# two_pieceboard_1.net
KiCad netlist of a schematic drawn in EAGLE
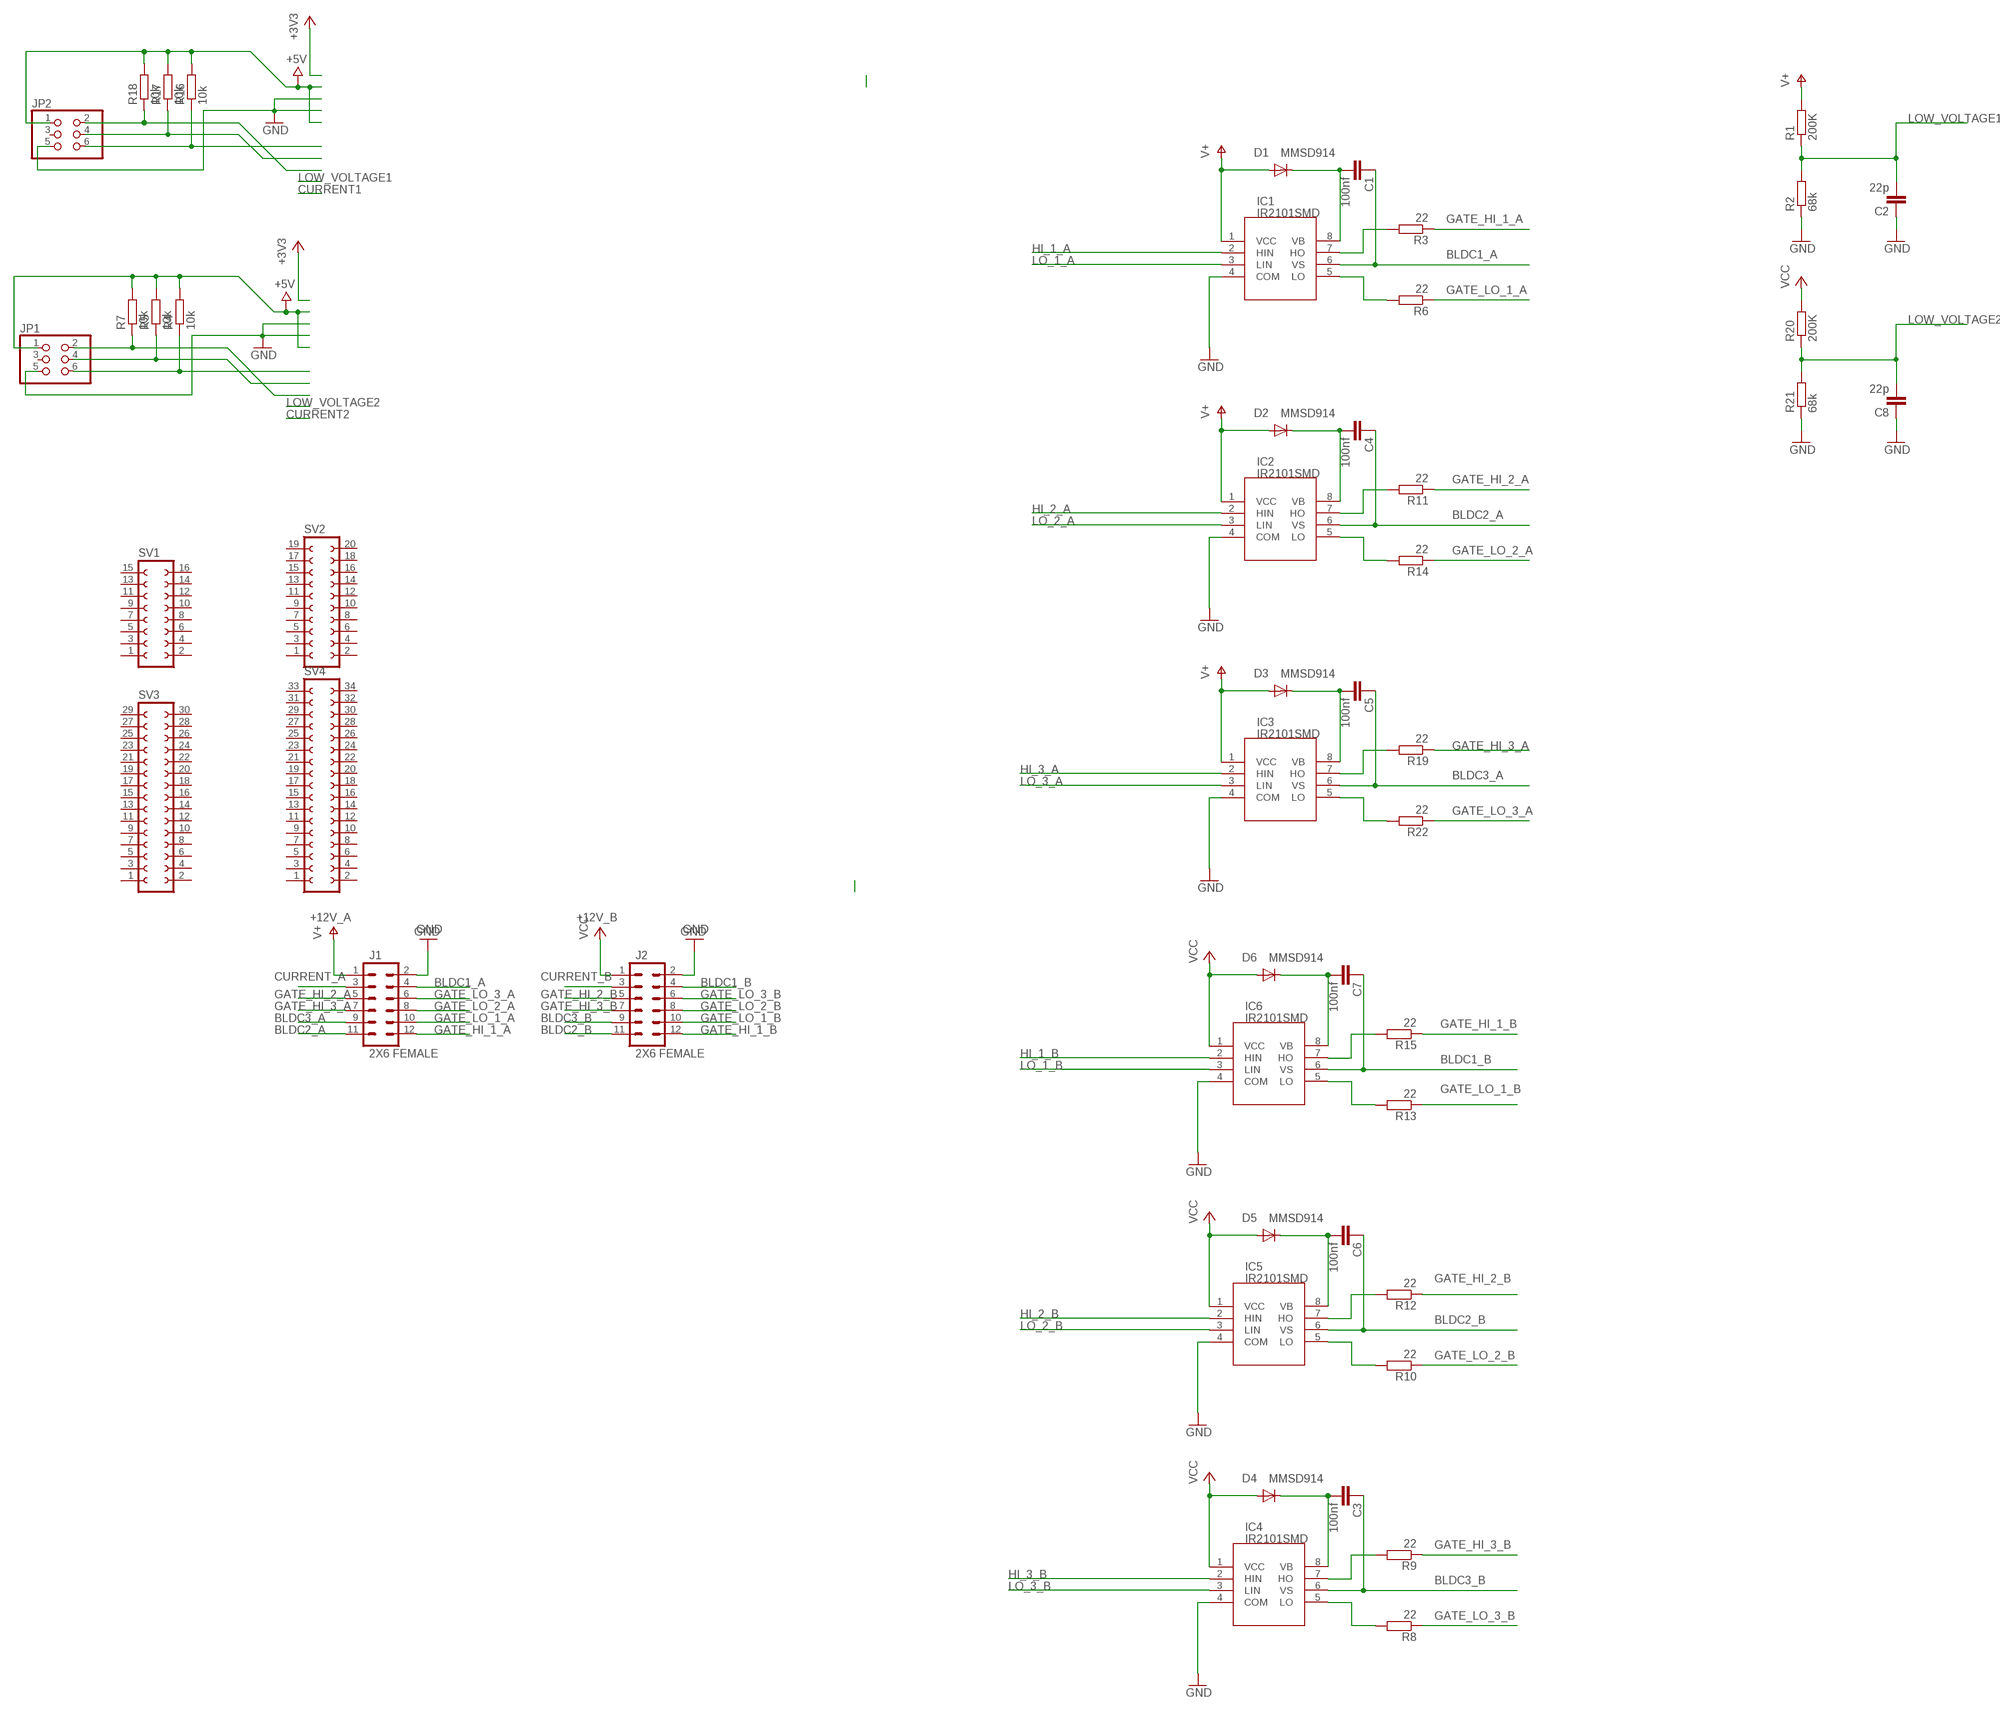
[diagram p0: schematic, sheet 1]

(export (version "E")
  (design (tool "Eeschema 10.0.6"))
  (components
    (comp (ref "C1")
      (value "100nf")
      (footprint "eagle-import:C1206")
      (libsource (lib "eagle-import") (part "C-EUC1206"))
    )
    (comp (ref "C2")
      (value "22p")
      (footprint "eagle-import:C1206")
      (libsource (lib "eagle-import") (part "C-EUC1206"))
    )
    (comp (ref "C3")
      (value "100nf")
      (footprint "eagle-import:C1206")
      (libsource (lib "eagle-import") (part "C-EUC1206"))
    )
    (comp (ref "C4")
      (value "100nf")
      (footprint "eagle-import:C1206")
      (libsource (lib "eagle-import") (part "C-EUC1206"))
    )
    (comp (ref "C5")
      (value "100nf")
      (footprint "eagle-import:C1206")
      (libsource (lib "eagle-import") (part "C-EUC1206"))
    )
    (comp (ref "C6")
      (value "100nf")
      (footprint "eagle-import:C1206")
      (libsource (lib "eagle-import") (part "C-EUC1206"))
    )
    (comp (ref "C7")
      (value "100nf")
      (footprint "eagle-import:C1206")
      (libsource (lib "eagle-import") (part "C-EUC1206"))
    )
    (comp (ref "C8")
      (value "22p")
      (footprint "eagle-import:C1206")
      (libsource (lib "eagle-import") (part "C-EUC1206"))
    )
    (comp (ref "D1")
      (value "MMSD914")
      (footprint "eagle-import:SOD123")
      (libsource (lib "eagle-import") (part "DIODE-SOD123"))
    )
    (comp (ref "D2")
      (value "MMSD914")
      (footprint "eagle-import:SOD123")
      (libsource (lib "eagle-import") (part "DIODE-SOD123"))
    )
    (comp (ref "D3")
      (value "MMSD914")
      (footprint "eagle-import:SOD123")
      (libsource (lib "eagle-import") (part "DIODE-SOD123"))
    )
    (comp (ref "D4")
      (value "MMSD914")
      (footprint "eagle-import:SOD123")
      (libsource (lib "eagle-import") (part "DIODE-SOD123"))
    )
    (comp (ref "D5")
      (value "MMSD914")
      (footprint "eagle-import:SOD123")
      (libsource (lib "eagle-import") (part "DIODE-SOD123"))
    )
    (comp (ref "D6")
      (value "MMSD914")
      (footprint "eagle-import:SOD123")
      (libsource (lib "eagle-import") (part "DIODE-SOD123"))
    )
    (comp (ref "IC1")
      (value "IR2101SMD")
      (footprint "eagle-import:SO08")
      (libsource (lib "eagle-import") (part "IR2101SMD"))
    )
    (comp (ref "IC2")
      (value "IR2101SMD")
      (footprint "eagle-import:SO08")
      (libsource (lib "eagle-import") (part "IR2101SMD"))
    )
    (comp (ref "IC3")
      (value "IR2101SMD")
      (footprint "eagle-import:SO08")
      (libsource (lib "eagle-import") (part "IR2101SMD"))
    )
    (comp (ref "IC4")
      (value "IR2101SMD")
      (footprint "eagle-import:SO08")
      (libsource (lib "eagle-import") (part "IR2101SMD"))
    )
    (comp (ref "IC5")
      (value "IR2101SMD")
      (footprint "eagle-import:SO08")
      (libsource (lib "eagle-import") (part "IR2101SMD"))
    )
    (comp (ref "IC6")
      (value "IR2101SMD")
      (footprint "eagle-import:SO08")
      (libsource (lib "eagle-import") (part "IR2101SMD"))
    )
    (comp (ref "J1")
      (value "2X6 FEMALE")
      (footprint "eagle-import:2X6")
      (libsource (lib "eagle-import") (part "M06X2PTH_FEMALE"))
    )
    (comp (ref "J2")
      (value "2X6 FEMALE")
      (footprint "eagle-import:2X6")
      (libsource (lib "eagle-import") (part "M06X2PTH_FEMALE"))
    )
    (comp (ref "JP1")
      (value "PINHD-2X3")
      (footprint "eagle-import:2X03")
      (libsource (lib "eagle-import") (part "PINHD-2X3"))
    )
    (comp (ref "JP2")
      (value "PINHD-2X3")
      (footprint "eagle-import:2X03")
      (libsource (lib "eagle-import") (part "PINHD-2X3"))
    )
    (comp (ref "R1")
      (value "200K")
      (footprint "eagle-import:R1206")
      (libsource (lib "eagle-import") (part "R-EU_R1206"))
    )
    (comp (ref "R2")
      (value "68k")
      (footprint "eagle-import:R1206")
      (libsource (lib "eagle-import") (part "R-EU_R1206"))
    )
    (comp (ref "R3")
      (value "22")
      (footprint "eagle-import:R1206")
      (libsource (lib "eagle-import") (part "R-EU_R1206"))
    )
    (comp (ref "R4")
      (value "10k")
      (footprint "eagle-import:R1206")
      (libsource (lib "eagle-import") (part "R-EU_R1206"))
    )
    (comp (ref "R5")
      (value "10k")
      (footprint "eagle-import:R1206")
      (libsource (lib "eagle-import") (part "R-EU_R1206"))
    )
    (comp (ref "R6")
      (value "22")
      (footprint "eagle-import:R1206")
      (libsource (lib "eagle-import") (part "R-EU_R1206"))
    )
    (comp (ref "R7")
      (value "10k")
      (footprint "eagle-import:R1206")
      (libsource (lib "eagle-import") (part "R-EU_R1206"))
    )
    (comp (ref "R8")
      (value "22")
      (footprint "eagle-import:R1206")
      (libsource (lib "eagle-import") (part "R-EU_R1206"))
    )
    (comp (ref "R9")
      (value "22")
      (footprint "eagle-import:R1206")
      (libsource (lib "eagle-import") (part "R-EU_R1206"))
    )
    (comp (ref "R10")
      (value "22")
      (footprint "eagle-import:R1206")
      (libsource (lib "eagle-import") (part "R-EU_R1206"))
    )
    (comp (ref "R11")
      (value "22")
      (footprint "eagle-import:R1206")
      (libsource (lib "eagle-import") (part "R-EU_R1206"))
    )
    (comp (ref "R12")
      (value "22")
      (footprint "eagle-import:R1206")
      (libsource (lib "eagle-import") (part "R-EU_R1206"))
    )
    (comp (ref "R13")
      (value "22")
      (footprint "eagle-import:R1206")
      (libsource (lib "eagle-import") (part "R-EU_R1206"))
    )
    (comp (ref "R14")
      (value "22")
      (footprint "eagle-import:R1206")
      (libsource (lib "eagle-import") (part "R-EU_R1206"))
    )
    (comp (ref "R15")
      (value "22")
      (footprint "eagle-import:R1206")
      (libsource (lib "eagle-import") (part "R-EU_R1206"))
    )
    (comp (ref "R16")
      (value "10k")
      (footprint "eagle-import:R1206")
      (libsource (lib "eagle-import") (part "R-EU_R1206"))
    )
    (comp (ref "R17")
      (value "10k")
      (footprint "eagle-import:R1206")
      (libsource (lib "eagle-import") (part "R-EU_R1206"))
    )
    (comp (ref "R18")
      (value "10k")
      (footprint "eagle-import:R1206")
      (libsource (lib "eagle-import") (part "R-EU_R1206"))
    )
    (comp (ref "R19")
      (value "22")
      (footprint "eagle-import:R1206")
      (libsource (lib "eagle-import") (part "R-EU_R1206"))
    )
    (comp (ref "R20")
      (value "200K")
      (footprint "eagle-import:R1206")
      (libsource (lib "eagle-import") (part "R-EU_R1206"))
    )
    (comp (ref "R21")
      (value "68k")
      (footprint "eagle-import:R1206")
      (libsource (lib "eagle-import") (part "R-EU_R1206"))
    )
    (comp (ref "R22")
      (value "22")
      (footprint "eagle-import:R1206")
      (libsource (lib "eagle-import") (part "R-EU_R1206"))
    )
    (comp (ref "SV1")
      (value "FE08-2")
      (footprint "eagle-import:FE08-2")
      (libsource (lib "eagle-import") (part "FE08-2"))
    )
    (comp (ref "SV2")
      (value "FE10-2")
      (footprint "eagle-import:FE10-2")
      (libsource (lib "eagle-import") (part "FE10-2"))
    )
    (comp (ref "SV3")
      (value "FE15-2")
      (footprint "eagle-import:FE15-2")
      (libsource (lib "eagle-import") (part "FE15-2"))
    )
    (comp (ref "SV4")
      (value "FE17-2")
      (footprint "eagle-import:FE17-2")
      (libsource (lib "eagle-import") (part "FE17-2"))
    )
  )
  (nets
    (net (code "2") (name "+5V") (class "Default")
      (node (ref "JP1") (pin "1") (pinfunction "1_1") (pintype "passive"))
      (node (ref "JP2") (pin "1") (pinfunction "1_1") (pintype "passive"))
      (node (ref "R16") (pin "2") (pinfunction "2_2") (pintype "passive"))
      (node (ref "R17") (pin "2") (pinfunction "2_2") (pintype "passive"))
      (node (ref "R18") (pin "2") (pinfunction "2_2") (pintype "passive"))
      (node (ref "R4") (pin "2") (pinfunction "2_2") (pintype "passive"))
      (node (ref "R5") (pin "2") (pinfunction "2_2") (pintype "passive"))
      (node (ref "R7") (pin "2") (pinfunction "2_2") (pintype "passive"))
    )
    (net (code "3") (name "/BLDC1_A") (class "Default")
      (node (ref "C1") (pin "1") (pinfunction "1_1") (pintype "passive"))
      (node (ref "IC1") (pin "6") (pinfunction "VS_6") (pintype "bidirectional"))
      (node (ref "J1") (pin "4") (pinfunction "4_4") (pintype "passive"))
    )
    (net (code "4") (name "/BLDC1_B") (class "Default")
      (node (ref "C7") (pin "1") (pinfunction "1_1") (pintype "passive"))
      (node (ref "IC6") (pin "6") (pinfunction "VS_6") (pintype "bidirectional"))
      (node (ref "J2") (pin "4") (pinfunction "4_4") (pintype "passive"))
    )
    (net (code "5") (name "/BLDC2_A") (class "Default")
      (node (ref "C4") (pin "1") (pinfunction "1_1") (pintype "passive"))
      (node (ref "IC2") (pin "6") (pinfunction "VS_6") (pintype "bidirectional"))
      (node (ref "J1") (pin "11") (pinfunction "11_11") (pintype "passive"))
    )
    (net (code "6") (name "/BLDC2_B") (class "Default")
      (node (ref "C6") (pin "1") (pinfunction "1_1") (pintype "passive"))
      (node (ref "IC5") (pin "6") (pinfunction "VS_6") (pintype "bidirectional"))
      (node (ref "J2") (pin "11") (pinfunction "11_11") (pintype "passive"))
    )
    (net (code "7") (name "/BLDC3_A") (class "Default")
      (node (ref "C5") (pin "1") (pinfunction "1_1") (pintype "passive"))
      (node (ref "IC3") (pin "6") (pinfunction "VS_6") (pintype "bidirectional"))
      (node (ref "J1") (pin "9") (pinfunction "9_9") (pintype "passive"))
    )
    (net (code "8") (name "/BLDC3_B") (class "Default")
      (node (ref "C3") (pin "1") (pinfunction "1_1") (pintype "passive"))
      (node (ref "IC4") (pin "6") (pinfunction "VS_6") (pintype "bidirectional"))
      (node (ref "J2") (pin "9") (pinfunction "9_9") (pintype "passive"))
    )
    (net (code "11") (name "/CURRENT_A") (class "Default")
      (node (ref "J1") (pin "3") (pinfunction "3_3") (pintype "passive"))
    )
    (net (code "12") (name "/CURRENT_B") (class "Default")
      (node (ref "J2") (pin "3") (pinfunction "3_3") (pintype "passive"))
    )
    (net (code "13") (name "/GATE_HI_1_A") (class "Default")
      (node (ref "J1") (pin "12") (pinfunction "12_12") (pintype "passive"))
      (node (ref "R3") (pin "1") (pinfunction "1_1") (pintype "passive"))
    )
    (net (code "14") (name "/GATE_HI_1_B") (class "Default")
      (node (ref "J2") (pin "12") (pinfunction "12_12") (pintype "passive"))
      (node (ref "R15") (pin "1") (pinfunction "1_1") (pintype "passive"))
    )
    (net (code "15") (name "/GATE_HI_2_A") (class "Default")
      (node (ref "J1") (pin "5") (pinfunction "5_5") (pintype "passive"))
      (node (ref "R11") (pin "1") (pinfunction "1_1") (pintype "passive"))
    )
    (net (code "16") (name "/GATE_HI_2_B") (class "Default")
      (node (ref "J2") (pin "5") (pinfunction "5_5") (pintype "passive"))
      (node (ref "R12") (pin "1") (pinfunction "1_1") (pintype "passive"))
    )
    (net (code "17") (name "/GATE_HI_3_A") (class "Default")
      (node (ref "J1") (pin "7") (pinfunction "7_7") (pintype "passive"))
      (node (ref "R19") (pin "1") (pinfunction "1_1") (pintype "passive"))
    )
    (net (code "18") (name "/GATE_HI_3_B") (class "Default")
      (node (ref "J2") (pin "7") (pinfunction "7_7") (pintype "passive"))
      (node (ref "R9") (pin "1") (pinfunction "1_1") (pintype "passive"))
    )
    (net (code "19") (name "/GATE_LO_1_A") (class "Default")
      (node (ref "J1") (pin "10") (pinfunction "10_10") (pintype "passive"))
      (node (ref "R6") (pin "1") (pinfunction "1_1") (pintype "passive"))
    )
    (net (code "20") (name "/GATE_LO_1_B") (class "Default")
      (node (ref "J2") (pin "10") (pinfunction "10_10") (pintype "passive"))
      (node (ref "R13") (pin "1") (pinfunction "1_1") (pintype "passive"))
    )
    (net (code "21") (name "/GATE_LO_2_A") (class "Default")
      (node (ref "J1") (pin "8") (pinfunction "8_8") (pintype "passive"))
      (node (ref "R14") (pin "1") (pinfunction "1_1") (pintype "passive"))
    )
    (net (code "22") (name "/GATE_LO_2_B") (class "Default")
      (node (ref "J2") (pin "8") (pinfunction "8_8") (pintype "passive"))
      (node (ref "R10") (pin "1") (pinfunction "1_1") (pintype "passive"))
    )
    (net (code "23") (name "/GATE_LO_3_A") (class "Default")
      (node (ref "J1") (pin "6") (pinfunction "6_6") (pintype "passive"))
      (node (ref "R22") (pin "1") (pinfunction "1_1") (pintype "passive"))
    )
    (net (code "24") (name "/GATE_LO_3_B") (class "Default")
      (node (ref "J2") (pin "6") (pinfunction "6_6") (pintype "passive"))
      (node (ref "R8") (pin "1") (pinfunction "1_1") (pintype "passive"))
    )
    (net (code "25") (name "/HI_1_A") (class "Default")
      (node (ref "IC1") (pin "2") (pinfunction "HIN_2") (pintype "bidirectional"))
    )
    (net (code "26") (name "/HI_1_B") (class "Default")
      (node (ref "IC6") (pin "2") (pinfunction "HIN_2") (pintype "bidirectional"))
    )
    (net (code "27") (name "/HI_2_A") (class "Default")
      (node (ref "IC2") (pin "2") (pinfunction "HIN_2") (pintype "bidirectional"))
    )
    (net (code "28") (name "/HI_2_B") (class "Default")
      (node (ref "IC5") (pin "2") (pinfunction "HIN_2") (pintype "bidirectional"))
    )
    (net (code "29") (name "/HI_3_A") (class "Default")
      (node (ref "IC3") (pin "2") (pinfunction "HIN_2") (pintype "bidirectional"))
    )
    (net (code "30") (name "/HI_3_B") (class "Default")
      (node (ref "IC4") (pin "2") (pinfunction "HIN_2") (pintype "bidirectional"))
    )
    (net (code "31") (name "/LOW_VOLTAGE1") (class "Default")
      (node (ref "C2") (pin "2") (pinfunction "2_2") (pintype "passive"))
      (node (ref "R1") (pin "1") (pinfunction "1_1") (pintype "passive"))
      (node (ref "R2") (pin "2") (pinfunction "2_2") (pintype "passive"))
    )
    (net (code "32") (name "/LOW_VOLTAGE2") (class "Default")
      (node (ref "C8") (pin "2") (pinfunction "2_2") (pintype "passive"))
      (node (ref "R20") (pin "1") (pinfunction "1_1") (pintype "passive"))
      (node (ref "R21") (pin "2") (pinfunction "2_2") (pintype "passive"))
    )
    (net (code "33") (name "/LO_1_A") (class "Default")
      (node (ref "IC1") (pin "3") (pinfunction "LIN_3") (pintype "bidirectional"))
    )
    (net (code "34") (name "/LO_1_B") (class "Default")
      (node (ref "IC6") (pin "3") (pinfunction "LIN_3") (pintype "bidirectional"))
    )
    (net (code "35") (name "/LO_2_A") (class "Default")
      (node (ref "IC2") (pin "3") (pinfunction "LIN_3") (pintype "bidirectional"))
    )
    (net (code "36") (name "/LO_2_B") (class "Default")
      (node (ref "IC5") (pin "3") (pinfunction "LIN_3") (pintype "bidirectional"))
    )
    (net (code "37") (name "/LO_3_A") (class "Default")
      (node (ref "IC3") (pin "3") (pinfunction "LIN_3") (pintype "bidirectional"))
    )
    (net (code "38") (name "/LO_3_B") (class "Default")
      (node (ref "IC4") (pin "3") (pinfunction "LIN_3") (pintype "bidirectional"))
    )
    (net (code "39") (name "GND") (class "Default")
      (node (ref "C2") (pin "1") (pinfunction "1_1") (pintype "passive"))
      (node (ref "C8") (pin "1") (pinfunction "1_1") (pintype "passive"))
      (node (ref "IC1") (pin "4") (pinfunction "COM_4") (pintype "bidirectional"))
      (node (ref "IC2") (pin "4") (pinfunction "COM_4") (pintype "bidirectional"))
      (node (ref "IC3") (pin "4") (pinfunction "COM_4") (pintype "bidirectional"))
      (node (ref "IC4") (pin "4") (pinfunction "COM_4") (pintype "bidirectional"))
      (node (ref "IC5") (pin "4") (pinfunction "COM_4") (pintype "bidirectional"))
      (node (ref "IC6") (pin "4") (pinfunction "COM_4") (pintype "bidirectional"))
      (node (ref "J1") (pin "2") (pinfunction "2_2") (pintype "passive"))
      (node (ref "J2") (pin "2") (pinfunction "2_2") (pintype "passive"))
      (node (ref "JP1") (pin "5") (pinfunction "5_5") (pintype "passive"))
      (node (ref "JP2") (pin "5") (pinfunction "5_5") (pintype "passive"))
      (node (ref "R2") (pin "1") (pinfunction "1_1") (pintype "passive"))
      (node (ref "R21") (pin "1") (pinfunction "1_1") (pintype "passive"))
    )
    (net (code "40") (name "Net-(IC1-HO)") (class "Default")
      (node (ref "IC1") (pin "7") (pinfunction "HO_7") (pintype "bidirectional"))
      (node (ref "R3") (pin "2") (pinfunction "2_2") (pintype "passive"))
    )
    (net (code "41") (name "Net-(IC1-LO)") (class "Default")
      (node (ref "IC1") (pin "5") (pinfunction "LO_5") (pintype "bidirectional"))
      (node (ref "R6") (pin "2") (pinfunction "2_2") (pintype "passive"))
    )
    (net (code "42") (name "Net-(IC1-VB)") (class "Default")
      (node (ref "C1") (pin "2") (pinfunction "2_2") (pintype "passive"))
      (node (ref "D1") (pin "C") (pinfunction "C_C") (pintype "passive"))
      (node (ref "IC1") (pin "8") (pinfunction "VB_8") (pintype "bidirectional"))
    )
    (net (code "43") (name "Net-(IC2-HO)") (class "Default")
      (node (ref "IC2") (pin "7") (pinfunction "HO_7") (pintype "bidirectional"))
      (node (ref "R11") (pin "2") (pinfunction "2_2") (pintype "passive"))
    )
    (net (code "44") (name "Net-(IC2-LO)") (class "Default")
      (node (ref "IC2") (pin "5") (pinfunction "LO_5") (pintype "bidirectional"))
      (node (ref "R14") (pin "2") (pinfunction "2_2") (pintype "passive"))
    )
    (net (code "45") (name "Net-(IC2-VB)") (class "Default")
      (node (ref "C4") (pin "2") (pinfunction "2_2") (pintype "passive"))
      (node (ref "D2") (pin "C") (pinfunction "C_C") (pintype "passive"))
      (node (ref "IC2") (pin "8") (pinfunction "VB_8") (pintype "bidirectional"))
    )
    (net (code "46") (name "Net-(IC3-HO)") (class "Default")
      (node (ref "IC3") (pin "7") (pinfunction "HO_7") (pintype "bidirectional"))
      (node (ref "R19") (pin "2") (pinfunction "2_2") (pintype "passive"))
    )
    (net (code "47") (name "Net-(IC3-LO)") (class "Default")
      (node (ref "IC3") (pin "5") (pinfunction "LO_5") (pintype "bidirectional"))
      (node (ref "R22") (pin "2") (pinfunction "2_2") (pintype "passive"))
    )
    (net (code "48") (name "Net-(IC3-VB)") (class "Default")
      (node (ref "C5") (pin "2") (pinfunction "2_2") (pintype "passive"))
      (node (ref "D3") (pin "C") (pinfunction "C_C") (pintype "passive"))
      (node (ref "IC3") (pin "8") (pinfunction "VB_8") (pintype "bidirectional"))
    )
    (net (code "49") (name "Net-(IC4-HO)") (class "Default")
      (node (ref "IC4") (pin "7") (pinfunction "HO_7") (pintype "bidirectional"))
      (node (ref "R9") (pin "2") (pinfunction "2_2") (pintype "passive"))
    )
    (net (code "50") (name "Net-(IC4-LO)") (class "Default")
      (node (ref "IC4") (pin "5") (pinfunction "LO_5") (pintype "bidirectional"))
      (node (ref "R8") (pin "2") (pinfunction "2_2") (pintype "passive"))
    )
    (net (code "51") (name "Net-(IC4-VB)") (class "Default")
      (node (ref "C3") (pin "2") (pinfunction "2_2") (pintype "passive"))
      (node (ref "D4") (pin "C") (pinfunction "C_C") (pintype "passive"))
      (node (ref "IC4") (pin "8") (pinfunction "VB_8") (pintype "bidirectional"))
    )
    (net (code "52") (name "Net-(IC5-HO)") (class "Default")
      (node (ref "IC5") (pin "7") (pinfunction "HO_7") (pintype "bidirectional"))
      (node (ref "R12") (pin "2") (pinfunction "2_2") (pintype "passive"))
    )
    (net (code "53") (name "Net-(IC5-LO)") (class "Default")
      (node (ref "IC5") (pin "5") (pinfunction "LO_5") (pintype "bidirectional"))
      (node (ref "R10") (pin "2") (pinfunction "2_2") (pintype "passive"))
    )
    (net (code "54") (name "Net-(IC5-VB)") (class "Default")
      (node (ref "C6") (pin "2") (pinfunction "2_2") (pintype "passive"))
      (node (ref "D5") (pin "C") (pinfunction "C_C") (pintype "passive"))
      (node (ref "IC5") (pin "8") (pinfunction "VB_8") (pintype "bidirectional"))
    )
    (net (code "55") (name "Net-(IC6-HO)") (class "Default")
      (node (ref "IC6") (pin "7") (pinfunction "HO_7") (pintype "bidirectional"))
      (node (ref "R15") (pin "2") (pinfunction "2_2") (pintype "passive"))
    )
    (net (code "56") (name "Net-(IC6-LO)") (class "Default")
      (node (ref "IC6") (pin "5") (pinfunction "LO_5") (pintype "bidirectional"))
      (node (ref "R13") (pin "2") (pinfunction "2_2") (pintype "passive"))
    )
    (net (code "57") (name "Net-(IC6-VB)") (class "Default")
      (node (ref "C7") (pin "2") (pinfunction "2_2") (pintype "passive"))
      (node (ref "D6") (pin "C") (pinfunction "C_C") (pintype "passive"))
      (node (ref "IC6") (pin "8") (pinfunction "VB_8") (pintype "bidirectional"))
    )
    (net (code "58") (name "Net-(JP1-Pad2)") (class "Default")
      (node (ref "JP1") (pin "2") (pinfunction "2_2") (pintype "passive"))
      (node (ref "R7") (pin "1") (pinfunction "1_1") (pintype "passive"))
    )
    (net (code "59") (name "Net-(JP1-Pad4)") (class "Default")
      (node (ref "JP1") (pin "4") (pinfunction "4_4") (pintype "passive"))
      (node (ref "R5") (pin "1") (pinfunction "1_1") (pintype "passive"))
    )
    (net (code "60") (name "Net-(JP1-Pad6)") (class "Default")
      (node (ref "JP1") (pin "6") (pinfunction "6_6") (pintype "passive"))
      (node (ref "R4") (pin "1") (pinfunction "1_1") (pintype "passive"))
    )
    (net (code "61") (name "Net-(JP2-Pad2)") (class "Default")
      (node (ref "JP2") (pin "2") (pinfunction "2_2") (pintype "passive"))
      (node (ref "R18") (pin "1") (pinfunction "1_1") (pintype "passive"))
    )
    (net (code "62") (name "Net-(JP2-Pad4)") (class "Default")
      (node (ref "JP2") (pin "4") (pinfunction "4_4") (pintype "passive"))
      (node (ref "R17") (pin "1") (pinfunction "1_1") (pintype "passive"))
    )
    (net (code "63") (name "Net-(JP2-Pad6)") (class "Default")
      (node (ref "JP2") (pin "6") (pinfunction "6_6") (pintype "passive"))
      (node (ref "R16") (pin "1") (pinfunction "1_1") (pintype "passive"))
    )
    (net (code "64") (name "V+") (class "Default")
      (node (ref "D1") (pin "A") (pinfunction "A_A") (pintype "passive"))
      (node (ref "D2") (pin "A") (pinfunction "A_A") (pintype "passive"))
      (node (ref "D3") (pin "A") (pinfunction "A_A") (pintype "passive"))
      (node (ref "IC1") (pin "1") (pinfunction "VCC_1") (pintype "bidirectional"))
      (node (ref "IC2") (pin "1") (pinfunction "VCC_1") (pintype "bidirectional"))
      (node (ref "IC3") (pin "1") (pinfunction "VCC_1") (pintype "bidirectional"))
      (node (ref "J1") (pin "1") (pinfunction "1_1") (pintype "passive"))
      (node (ref "R1") (pin "2") (pinfunction "2_2") (pintype "passive"))
    )
    (net (code "65") (name "VCC") (class "Default")
      (node (ref "D4") (pin "A") (pinfunction "A_A") (pintype "passive"))
      (node (ref "D5") (pin "A") (pinfunction "A_A") (pintype "passive"))
      (node (ref "D6") (pin "A") (pinfunction "A_A") (pintype "passive"))
      (node (ref "IC4") (pin "1") (pinfunction "VCC_1") (pintype "bidirectional"))
      (node (ref "IC5") (pin "1") (pinfunction "VCC_1") (pintype "bidirectional"))
      (node (ref "IC6") (pin "1") (pinfunction "VCC_1") (pintype "bidirectional"))
      (node (ref "J2") (pin "1") (pinfunction "1_1") (pintype "passive"))
      (node (ref "R20") (pin "2") (pinfunction "2_2") (pintype "passive"))
    )
    (net (code "66") (name "unconnected-(JP1-Pad3)") (class "Default")
      (node (ref "JP1") (pin "3") (pinfunction "3_3") (pintype "passive"))
    )
    (net (code "67") (name "unconnected-(JP2-Pad3)") (class "Default")
      (node (ref "JP2") (pin "3") (pinfunction "3_3") (pintype "passive"))
    )
    (net (code "68") (name "unconnected-(SV1-Pad1)") (class "Default")
      (node (ref "SV1") (pin "1") (pinfunction "1_1") (pintype "passive"))
    )
    (net (code "69") (name "unconnected-(SV1-Pad2)") (class "Default")
      (node (ref "SV1") (pin "2") (pinfunction "2_2") (pintype "passive"))
    )
    (net (code "70") (name "unconnected-(SV1-Pad3)") (class "Default")
      (node (ref "SV1") (pin "3") (pinfunction "3_3") (pintype "passive"))
    )
    (net (code "71") (name "unconnected-(SV1-Pad4)") (class "Default")
      (node (ref "SV1") (pin "4") (pinfunction "4_4") (pintype "passive"))
    )
    (net (code "72") (name "unconnected-(SV1-Pad5)") (class "Default")
      (node (ref "SV1") (pin "5") (pinfunction "5_5") (pintype "passive"))
    )
    (net (code "73") (name "unconnected-(SV1-Pad6)") (class "Default")
      (node (ref "SV1") (pin "6") (pinfunction "6_6") (pintype "passive"))
    )
    (net (code "74") (name "unconnected-(SV1-Pad7)") (class "Default")
      (node (ref "SV1") (pin "7") (pinfunction "7_7") (pintype "passive"))
    )
    (net (code "75") (name "unconnected-(SV1-Pad8)") (class "Default")
      (node (ref "SV1") (pin "8") (pinfunction "8_8") (pintype "passive"))
    )
    (net (code "76") (name "unconnected-(SV1-Pad9)") (class "Default")
      (node (ref "SV1") (pin "9") (pinfunction "9_9") (pintype "passive"))
    )
    (net (code "77") (name "unconnected-(SV1-Pad10)") (class "Default")
      (node (ref "SV1") (pin "10") (pinfunction "10_10") (pintype "passive"))
    )
    (net (code "78") (name "unconnected-(SV1-Pad11)") (class "Default")
      (node (ref "SV1") (pin "11") (pinfunction "11_11") (pintype "passive"))
    )
    (net (code "79") (name "unconnected-(SV1-Pad12)") (class "Default")
      (node (ref "SV1") (pin "12") (pinfunction "12_12") (pintype "passive"))
    )
    (net (code "80") (name "unconnected-(SV1-Pad13)") (class "Default")
      (node (ref "SV1") (pin "13") (pinfunction "13_13") (pintype "passive"))
    )
    (net (code "81") (name "unconnected-(SV1-Pad14)") (class "Default")
      (node (ref "SV1") (pin "14") (pinfunction "14_14") (pintype "passive"))
    )
    (net (code "82") (name "unconnected-(SV1-Pad15)") (class "Default")
      (node (ref "SV1") (pin "15") (pinfunction "15_15") (pintype "passive"))
    )
    (net (code "83") (name "unconnected-(SV1-Pad16)") (class "Default")
      (node (ref "SV1") (pin "16") (pinfunction "16_16") (pintype "passive"))
    )
    (net (code "84") (name "unconnected-(SV2-Pad1)") (class "Default")
      (node (ref "SV2") (pin "1") (pinfunction "1_1") (pintype "passive"))
    )
    (net (code "85") (name "unconnected-(SV2-Pad2)") (class "Default")
      (node (ref "SV2") (pin "2") (pinfunction "2_2") (pintype "passive"))
    )
    (net (code "86") (name "unconnected-(SV2-Pad3)") (class "Default")
      (node (ref "SV2") (pin "3") (pinfunction "3_3") (pintype "passive"))
    )
    (net (code "87") (name "unconnected-(SV2-Pad4)") (class "Default")
      (node (ref "SV2") (pin "4") (pinfunction "4_4") (pintype "passive"))
    )
    (net (code "88") (name "unconnected-(SV2-Pad5)") (class "Default")
      (node (ref "SV2") (pin "5") (pinfunction "5_5") (pintype "passive"))
    )
    (net (code "89") (name "unconnected-(SV2-Pad6)") (class "Default")
      (node (ref "SV2") (pin "6") (pinfunction "6_6") (pintype "passive"))
    )
    (net (code "90") (name "unconnected-(SV2-Pad7)") (class "Default")
      (node (ref "SV2") (pin "7") (pinfunction "7_7") (pintype "passive"))
    )
    (net (code "91") (name "unconnected-(SV2-Pad8)") (class "Default")
      (node (ref "SV2") (pin "8") (pinfunction "8_8") (pintype "passive"))
    )
    (net (code "92") (name "unconnected-(SV2-Pad9)") (class "Default")
      (node (ref "SV2") (pin "9") (pinfunction "9_9") (pintype "passive"))
    )
    (net (code "93") (name "unconnected-(SV2-Pad10)") (class "Default")
      (node (ref "SV2") (pin "10") (pinfunction "10_10") (pintype "passive"))
    )
    (net (code "94") (name "unconnected-(SV2-Pad11)") (class "Default")
      (node (ref "SV2") (pin "11") (pinfunction "11_11") (pintype "passive"))
    )
    (net (code "95") (name "unconnected-(SV2-Pad12)") (class "Default")
      (node (ref "SV2") (pin "12") (pinfunction "12_12") (pintype "passive"))
    )
    (net (code "96") (name "unconnected-(SV2-Pad13)") (class "Default")
      (node (ref "SV2") (pin "13") (pinfunction "13_13") (pintype "passive"))
    )
    (net (code "97") (name "unconnected-(SV2-Pad14)") (class "Default")
      (node (ref "SV2") (pin "14") (pinfunction "14_14") (pintype "passive"))
    )
    (net (code "98") (name "unconnected-(SV2-Pad15)") (class "Default")
      (node (ref "SV2") (pin "15") (pinfunction "15_15") (pintype "passive"))
    )
    (net (code "99") (name "unconnected-(SV2-Pad16)") (class "Default")
      (node (ref "SV2") (pin "16") (pinfunction "16_16") (pintype "passive"))
    )
    (net (code "100") (name "unconnected-(SV2-Pad17)") (class "Default")
      (node (ref "SV2") (pin "17") (pinfunction "17_17") (pintype "passive"))
    )
    (net (code "101") (name "unconnected-(SV2-Pad18)") (class "Default")
      (node (ref "SV2") (pin "18") (pinfunction "18_18") (pintype "passive"))
    )
    (net (code "102") (name "unconnected-(SV2-Pad19)") (class "Default")
      (node (ref "SV2") (pin "19") (pinfunction "19_19") (pintype "passive"))
    )
    (net (code "103") (name "unconnected-(SV2-Pad20)") (class "Default")
      (node (ref "SV2") (pin "20") (pinfunction "20_20") (pintype "passive"))
    )
    (net (code "104") (name "unconnected-(SV3-Pad1)") (class "Default")
      (node (ref "SV3") (pin "1") (pinfunction "1_1") (pintype "passive"))
    )
    (net (code "105") (name "unconnected-(SV3-Pad2)") (class "Default")
      (node (ref "SV3") (pin "2") (pinfunction "2_2") (pintype "passive"))
    )
    (net (code "106") (name "unconnected-(SV3-Pad3)") (class "Default")
      (node (ref "SV3") (pin "3") (pinfunction "3_3") (pintype "passive"))
    )
    (net (code "107") (name "unconnected-(SV3-Pad4)") (class "Default")
      (node (ref "SV3") (pin "4") (pinfunction "4_4") (pintype "passive"))
    )
    (net (code "108") (name "unconnected-(SV3-Pad5)") (class "Default")
      (node (ref "SV3") (pin "5") (pinfunction "5_5") (pintype "passive"))
    )
    (net (code "109") (name "unconnected-(SV3-Pad6)") (class "Default")
      (node (ref "SV3") (pin "6") (pinfunction "6_6") (pintype "passive"))
    )
    (net (code "110") (name "unconnected-(SV3-Pad7)") (class "Default")
      (node (ref "SV3") (pin "7") (pinfunction "7_7") (pintype "passive"))
    )
    (net (code "111") (name "unconnected-(SV3-Pad8)") (class "Default")
      (node (ref "SV3") (pin "8") (pinfunction "8_8") (pintype "passive"))
    )
    (net (code "112") (name "unconnected-(SV3-Pad9)") (class "Default")
      (node (ref "SV3") (pin "9") (pinfunction "9_9") (pintype "passive"))
    )
    (net (code "113") (name "unconnected-(SV3-Pad10)") (class "Default")
      (node (ref "SV3") (pin "10") (pinfunction "10_10") (pintype "passive"))
    )
    (net (code "114") (name "unconnected-(SV3-Pad11)") (class "Default")
      (node (ref "SV3") (pin "11") (pinfunction "11_11") (pintype "passive"))
    )
    (net (code "115") (name "unconnected-(SV3-Pad12)") (class "Default")
      (node (ref "SV3") (pin "12") (pinfunction "12_12") (pintype "passive"))
    )
    (net (code "116") (name "unconnected-(SV3-Pad13)") (class "Default")
      (node (ref "SV3") (pin "13") (pinfunction "13_13") (pintype "passive"))
    )
    (net (code "117") (name "unconnected-(SV3-Pad14)") (class "Default")
      (node (ref "SV3") (pin "14") (pinfunction "14_14") (pintype "passive"))
    )
    (net (code "118") (name "unconnected-(SV3-Pad15)") (class "Default")
      (node (ref "SV3") (pin "15") (pinfunction "15_15") (pintype "passive"))
    )
    (net (code "119") (name "unconnected-(SV3-Pad16)") (class "Default")
      (node (ref "SV3") (pin "16") (pinfunction "16_16") (pintype "passive"))
    )
    (net (code "120") (name "unconnected-(SV3-Pad17)") (class "Default")
      (node (ref "SV3") (pin "17") (pinfunction "17_17") (pintype "passive"))
    )
    (net (code "121") (name "unconnected-(SV3-Pad18)") (class "Default")
      (node (ref "SV3") (pin "18") (pinfunction "18_18") (pintype "passive"))
    )
    (net (code "122") (name "unconnected-(SV3-Pad19)") (class "Default")
      (node (ref "SV3") (pin "19") (pinfunction "19_19") (pintype "passive"))
    )
    (net (code "123") (name "unconnected-(SV3-Pad20)") (class "Default")
      (node (ref "SV3") (pin "20") (pinfunction "20_20") (pintype "passive"))
    )
    (net (code "124") (name "unconnected-(SV3-Pad21)") (class "Default")
      (node (ref "SV3") (pin "21") (pinfunction "21_21") (pintype "passive"))
    )
    (net (code "125") (name "unconnected-(SV3-Pad22)") (class "Default")
      (node (ref "SV3") (pin "22") (pinfunction "22_22") (pintype "passive"))
    )
    (net (code "126") (name "unconnected-(SV3-Pad23)") (class "Default")
      (node (ref "SV3") (pin "23") (pinfunction "23_23") (pintype "passive"))
    )
    (net (code "127") (name "unconnected-(SV3-Pad24)") (class "Default")
      (node (ref "SV3") (pin "24") (pinfunction "24_24") (pintype "passive"))
    )
    (net (code "128") (name "unconnected-(SV3-Pad25)") (class "Default")
      (node (ref "SV3") (pin "25") (pinfunction "25_25") (pintype "passive"))
    )
    (net (code "129") (name "unconnected-(SV3-Pad26)") (class "Default")
      (node (ref "SV3") (pin "26") (pinfunction "26_26") (pintype "passive"))
    )
    (net (code "130") (name "unconnected-(SV3-Pad27)") (class "Default")
      (node (ref "SV3") (pin "27") (pinfunction "27_27") (pintype "passive"))
    )
    (net (code "131") (name "unconnected-(SV3-Pad28)") (class "Default")
      (node (ref "SV3") (pin "28") (pinfunction "28_28") (pintype "passive"))
    )
    (net (code "132") (name "unconnected-(SV3-Pad29)") (class "Default")
      (node (ref "SV3") (pin "29") (pinfunction "29_29") (pintype "passive"))
    )
    (net (code "133") (name "unconnected-(SV3-Pad30)") (class "Default")
      (node (ref "SV3") (pin "30") (pinfunction "30_30") (pintype "passive"))
    )
    (net (code "134") (name "unconnected-(SV4-Pad1)") (class "Default")
      (node (ref "SV4") (pin "1") (pinfunction "1_1") (pintype "passive"))
    )
    (net (code "135") (name "unconnected-(SV4-Pad2)") (class "Default")
      (node (ref "SV4") (pin "2") (pinfunction "2_2") (pintype "passive"))
    )
    (net (code "136") (name "unconnected-(SV4-Pad3)") (class "Default")
      (node (ref "SV4") (pin "3") (pinfunction "3_3") (pintype "passive"))
    )
    (net (code "137") (name "unconnected-(SV4-Pad4)") (class "Default")
      (node (ref "SV4") (pin "4") (pinfunction "4_4") (pintype "passive"))
    )
    (net (code "138") (name "unconnected-(SV4-Pad5)") (class "Default")
      (node (ref "SV4") (pin "5") (pinfunction "5_5") (pintype "passive"))
    )
    (net (code "139") (name "unconnected-(SV4-Pad6)") (class "Default")
      (node (ref "SV4") (pin "6") (pinfunction "6_6") (pintype "passive"))
    )
    (net (code "140") (name "unconnected-(SV4-Pad7)") (class "Default")
      (node (ref "SV4") (pin "7") (pinfunction "7_7") (pintype "passive"))
    )
    (net (code "141") (name "unconnected-(SV4-Pad8)") (class "Default")
      (node (ref "SV4") (pin "8") (pinfunction "8_8") (pintype "passive"))
    )
    (net (code "142") (name "unconnected-(SV4-Pad9)") (class "Default")
      (node (ref "SV4") (pin "9") (pinfunction "9_9") (pintype "passive"))
    )
    (net (code "143") (name "unconnected-(SV4-Pad10)") (class "Default")
      (node (ref "SV4") (pin "10") (pinfunction "10_10") (pintype "passive"))
    )
    (net (code "144") (name "unconnected-(SV4-Pad11)") (class "Default")
      (node (ref "SV4") (pin "11") (pinfunction "11_11") (pintype "passive"))
    )
    (net (code "145") (name "unconnected-(SV4-Pad12)") (class "Default")
      (node (ref "SV4") (pin "12") (pinfunction "12_12") (pintype "passive"))
    )
    (net (code "146") (name "unconnected-(SV4-Pad13)") (class "Default")
      (node (ref "SV4") (pin "13") (pinfunction "13_13") (pintype "passive"))
    )
    (net (code "147") (name "unconnected-(SV4-Pad14)") (class "Default")
      (node (ref "SV4") (pin "14") (pinfunction "14_14") (pintype "passive"))
    )
    (net (code "148") (name "unconnected-(SV4-Pad15)") (class "Default")
      (node (ref "SV4") (pin "15") (pinfunction "15_15") (pintype "passive"))
    )
    (net (code "149") (name "unconnected-(SV4-Pad16)") (class "Default")
      (node (ref "SV4") (pin "16") (pinfunction "16_16") (pintype "passive"))
    )
    (net (code "150") (name "unconnected-(SV4-Pad17)") (class "Default")
      (node (ref "SV4") (pin "17") (pinfunction "17_17") (pintype "passive"))
    )
    (net (code "151") (name "unconnected-(SV4-Pad18)") (class "Default")
      (node (ref "SV4") (pin "18") (pinfunction "18_18") (pintype "passive"))
    )
    (net (code "152") (name "unconnected-(SV4-Pad19)") (class "Default")
      (node (ref "SV4") (pin "19") (pinfunction "19_19") (pintype "passive"))
    )
    (net (code "153") (name "unconnected-(SV4-Pad20)") (class "Default")
      (node (ref "SV4") (pin "20") (pinfunction "20_20") (pintype "passive"))
    )
    (net (code "154") (name "unconnected-(SV4-Pad21)") (class "Default")
      (node (ref "SV4") (pin "21") (pinfunction "21_21") (pintype "passive"))
    )
    (net (code "155") (name "unconnected-(SV4-Pad22)") (class "Default")
      (node (ref "SV4") (pin "22") (pinfunction "22_22") (pintype "passive"))
    )
    (net (code "156") (name "unconnected-(SV4-Pad23)") (class "Default")
      (node (ref "SV4") (pin "23") (pinfunction "23_23") (pintype "passive"))
    )
    (net (code "157") (name "unconnected-(SV4-Pad24)") (class "Default")
      (node (ref "SV4") (pin "24") (pinfunction "24_24") (pintype "passive"))
    )
    (net (code "158") (name "unconnected-(SV4-Pad25)") (class "Default")
      (node (ref "SV4") (pin "25") (pinfunction "25_25") (pintype "passive"))
    )
    (net (code "159") (name "unconnected-(SV4-Pad26)") (class "Default")
      (node (ref "SV4") (pin "26") (pinfunction "26_26") (pintype "passive"))
    )
    (net (code "160") (name "unconnected-(SV4-Pad27)") (class "Default")
      (node (ref "SV4") (pin "27") (pinfunction "27_27") (pintype "passive"))
    )
    (net (code "161") (name "unconnected-(SV4-Pad28)") (class "Default")
      (node (ref "SV4") (pin "28") (pinfunction "28_28") (pintype "passive"))
    )
    (net (code "162") (name "unconnected-(SV4-Pad29)") (class "Default")
      (node (ref "SV4") (pin "29") (pinfunction "29_29") (pintype "passive"))
    )
    (net (code "163") (name "unconnected-(SV4-Pad30)") (class "Default")
      (node (ref "SV4") (pin "30") (pinfunction "30_30") (pintype "passive"))
    )
    (net (code "164") (name "unconnected-(SV4-Pad31)") (class "Default")
      (node (ref "SV4") (pin "31") (pinfunction "31_31") (pintype "passive"))
    )
    (net (code "165") (name "unconnected-(SV4-Pad32)") (class "Default")
      (node (ref "SV4") (pin "32") (pinfunction "32_32") (pintype "passive"))
    )
    (net (code "166") (name "unconnected-(SV4-Pad33)") (class "Default")
      (node (ref "SV4") (pin "33") (pinfunction "33_33") (pintype "passive"))
    )
    (net (code "167") (name "unconnected-(SV4-Pad34)") (class "Default")
      (node (ref "SV4") (pin "34") (pinfunction "34_34") (pintype "passive"))
    )
  )
)
